# 01_MCU_ESP32C6.net
KiCad netlist of a schematic drawn in Altium Designer
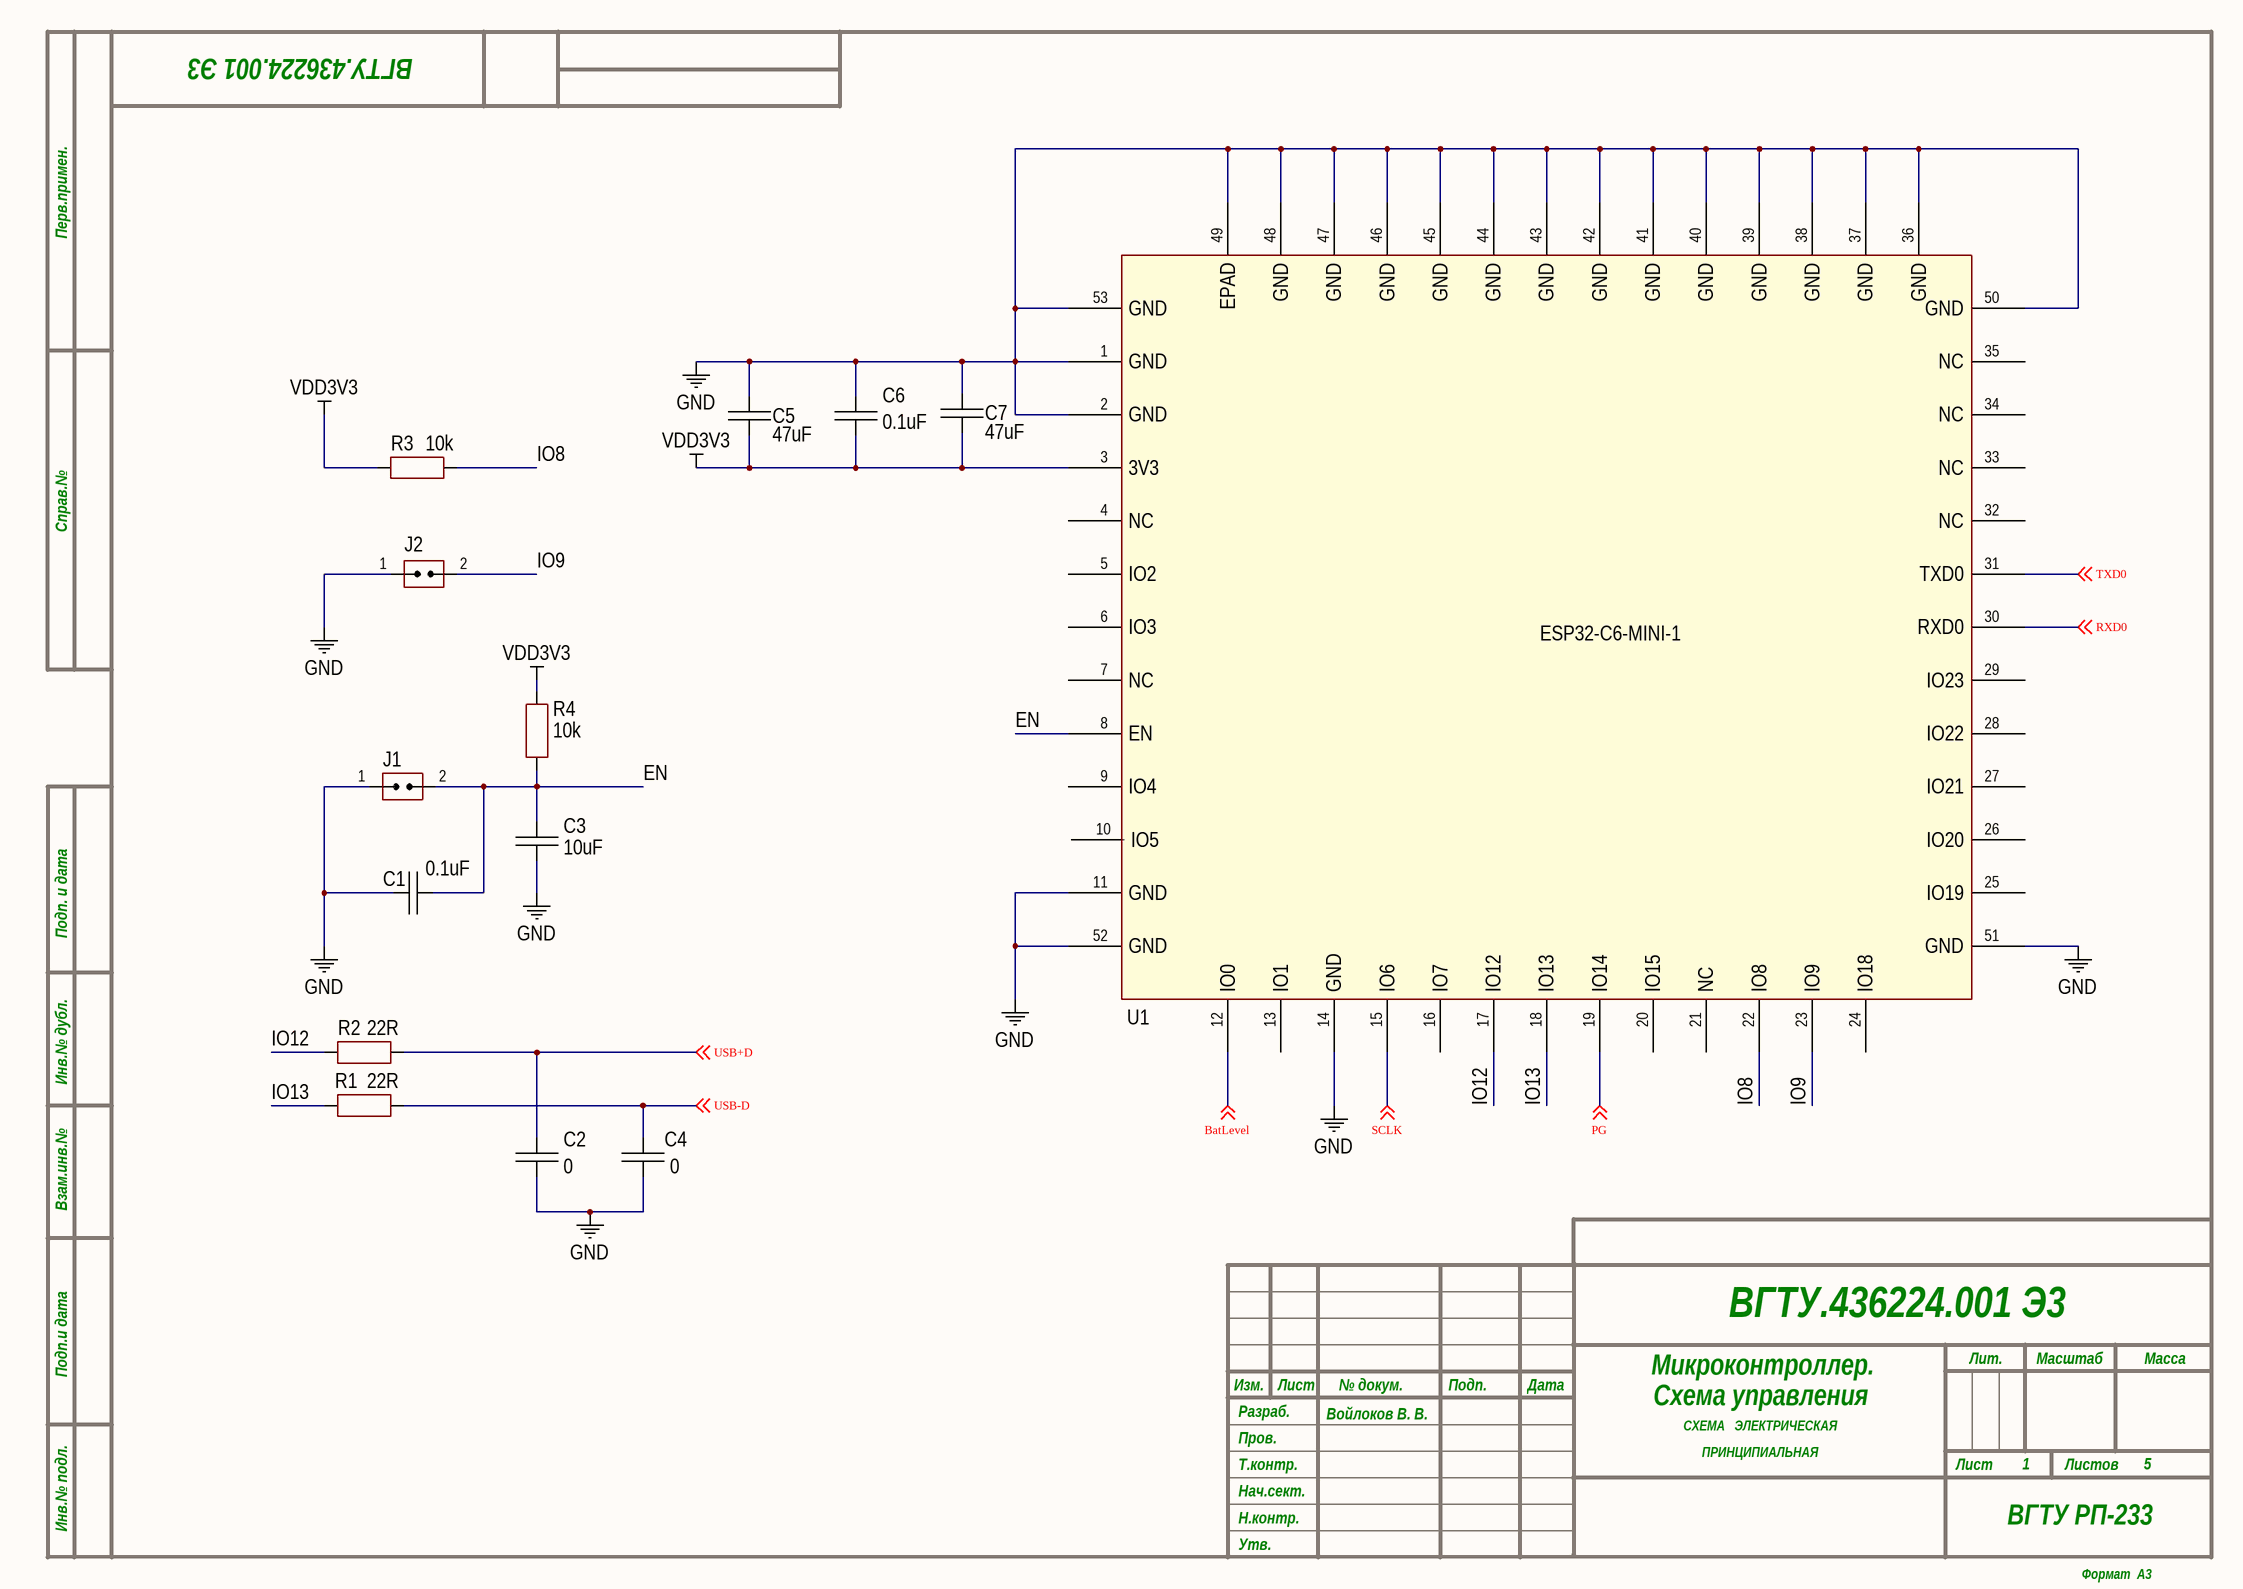
[diagram p0: 01_MCU_ESP32C6.SchDoc]

(export (version "E")
  (design (tool "Eeschema 10.0.6"))
  (components
    (comp (ref "C1")
      (value "0.1uF")
      (footprint "CAP: 0603")
      (fields
        (field (name "MANUFACTURER") "Yageo")
        (field (name "PARTNUMBER") "CC0603KRX7R7BB104")
        (field (name "VALUEMANUFACTURERPARTNUMBER") "Ceramic capacitor, 0.1uF, X7R, ±10%, 16V, 0603, -55...+125°C")
      )
      (libsource (lib "capacitor") (part "Ceramic_0603"))
    )
    (comp (ref "C2")
      (value "0")
      (footprint "CAP: 0603")
      (fields
        (field (name "MANUFACTURER") "Yageo")
        (field (name "PARTNUMBER") "CC0603KRX7R7BB104")
        (field (name "VALUEMANUFACTURERPARTNUMBER") "Ceramic capacitor, 0, X7R, ±10%, 16V, 0603, -55...+125°C")
      )
      (libsource (lib "capacitor") (part "Ceramic_0603"))
    )
    (comp (ref "C3")
      (value "10uF")
      (footprint "CAP: 0603")
      (fields
        (field (name "MANUFACTURER") "Yageo")
        (field (name "PARTNUMBER") "CC0603KRX7R7BB104")
        (field (name "VALUEMANUFACTURERPARTNUMBER") "Ceramic capacitor, 10uF, X7R, ±10%, 16V, 0603, -55...+125°C")
      )
      (libsource (lib "capacitor") (part "Ceramic_0603"))
    )
    (comp (ref "C4")
      (value "0")
      (footprint "CAP: 0603")
      (fields
        (field (name "MANUFACTURER") "Yageo")
        (field (name "PARTNUMBER") "CC0603KRX7R7BB104")
        (field (name "VALUEMANUFACTURERPARTNUMBER") "Ceramic capacitor, 0, X7R, ±10%, 16V, 0603, -55...+125°C")
      )
      (libsource (lib "capacitor") (part "Ceramic_0603"))
    )
    (comp (ref "C5")
      (value "47uF")
      (footprint "CAP: 0805")
      (fields
        (field (name "MANUFACTURER") "Yageo")
        (field (name "PARTNUMBER") "CC0805KRX7R7BB104")
        (field (name "VALUEMANUFACTURERPARTNUMBER") "Ceramic capacitor, 47uF, X7R, ±10%, 16V, 0805, -55...+125°C")
      )
      (libsource (lib "capacitor") (part "Ceramic_0805"))
    )
    (comp (ref "C6")
      (value "0.1uF")
      (footprint "CAP: 0603")
      (fields
        (field (name "MANUFACTURER") "Yageo")
        (field (name "PARTNUMBER") "CC0603KRX7R7BB104")
        (field (name "VALUEMANUFACTURERPARTNUMBER") "Ceramic capacitor, 0.1uF, X7R, ±10%, 16V, 0603, -55...+125°C")
      )
      (libsource (lib "capacitor") (part "Ceramic_0603"))
    )
    (comp (ref "C7")
      (value "47uF")
      (footprint "CAP: 0805")
      (fields
        (field (name "MANUFACTURER") "Yageo")
        (field (name "PARTNUMBER") "CC0805KRX7R7BB104")
        (field (name "VALUEMANUFACTURERPARTNUMBER") "Ceramic capacitor, 47uF, X7R, ±10%, 16V, 0805, -55...+125°C")
      )
      (libsource (lib "capacitor") (part "Ceramic_0805"))
    )
    (comp (ref "J1")
      (value "~")
      (footprint "CON: JUMPER x1")
      (libsource (lib "connector") (part "Jumper_single"))
    )
    (comp (ref "J2")
      (value "~")
      (footprint "CON: JUMPER x1")
      (libsource (lib "connector") (part "Jumper_single"))
    )
    (comp (ref "R1")
      (value "22R")
      (footprint "RES: 0603")
      (fields
        (field (name "MANUFACTURER") "Yageo")
        (field (name "PARTNUMBER") "RC0603JR-07100RL")
        (field (name "VALUEMANUFACTURERPARTNUMBER") "Resistor film, 22R, ±5%, 0603, 0.1W, -55...+125°C")
      )
      (libsource (lib "resistor") (part "Resistor_0603"))
    )
    (comp (ref "R2")
      (value "22R")
      (footprint "RES: 0603")
      (fields
        (field (name "MANUFACTURER") "Yageo")
        (field (name "PARTNUMBER") "RC0603JR-07100RL")
        (field (name "VALUEMANUFACTURERPARTNUMBER") "Resistor film, 22R, ±5%, 0603, 0.1W, -55...+125°C")
      )
      (libsource (lib "resistor") (part "Resistor_0603"))
    )
    (comp (ref "R3")
      (value "10k")
      (footprint "RES: 0603")
      (fields
        (field (name "MANUFACTURER") "Yageo")
        (field (name "PARTNUMBER") "RC0603JR-07100RL")
        (field (name "VALUEMANUFACTURERPARTNUMBER") "Resistor film, 10k, ±5%, 0603, 0.1W, -55...+125°C")
      )
      (libsource (lib "resistor") (part "Resistor_0603"))
    )
    (comp (ref "R4")
      (value "10k")
      (footprint "RES: 0603")
      (fields
        (field (name "MANUFACTURER") "Yageo")
        (field (name "PARTNUMBER") "RC0603JR-07100RL")
        (field (name "VALUEMANUFACTURERPARTNUMBER") "Resistor film, 10k, ±5%, 0603, 0.1W, -55...+125°C")
      )
      (libsource (lib "") (part "Resistor_0603_1"))
    )
    (comp (ref "U1")
      (value "ESP32-C6-MINI-1")
      (footprint "ESP32-C6_EXP")
      (libsource (lib "MyLib") (part "ESP32-C6-MINI-1"))
    )
  )
  (nets
    (net (code "1") (name "/EN") (class "Default")
      (node (ref "C1") (pin "1") (pinfunction "1_1") (pintype "passive"))
      (node (ref "C3") (pin "2") (pinfunction "2_2") (pintype "passive"))
      (node (ref "J1") (pin "2") (pinfunction "IN_2") (pintype "passive"))
      (node (ref "R4") (pin "1") (pinfunction "1_1") (pintype "passive"))
      (node (ref "U1") (pin "8") (pinfunction "EN_8") (pintype "passive"))
    )
    (net (code "2") (name "/IO8") (class "Default")
      (node (ref "R3") (pin "1") (pinfunction "1_1") (pintype "passive"))
      (node (ref "U1") (pin "22") (pinfunction "IO8_22") (pintype "passive"))
    )
    (net (code "3") (name "/IO9") (class "Default")
      (node (ref "J2") (pin "2") (pinfunction "IN_2") (pintype "passive"))
      (node (ref "U1") (pin "23") (pinfunction "IO9_23") (pintype "passive"))
    )
    (net (code "4") (name "/IO12") (class "Default")
      (node (ref "R2") (pin "2") (pinfunction "2_2") (pintype "passive"))
      (node (ref "U1") (pin "17") (pinfunction "IO12_17") (pintype "passive"))
    )
    (net (code "5") (name "/IO13") (class "Default")
      (node (ref "R1") (pin "2") (pinfunction "2_2") (pintype "passive"))
      (node (ref "U1") (pin "18") (pinfunction "IO13_18") (pintype "passive"))
    )
    (net (code "6") (name "BatLevel") (class "Default")
      (node (ref "U1") (pin "12") (pinfunction "IO0_12") (pintype "passive"))
    )
    (net (code "7") (name "GND") (class "Default")
      (node (ref "C1") (pin "2") (pinfunction "2_2") (pintype "passive"))
      (node (ref "C2") (pin "2") (pinfunction "2_2") (pintype "passive"))
      (node (ref "C3") (pin "1") (pinfunction "1_1") (pintype "passive"))
      (node (ref "C4") (pin "2") (pinfunction "2_2") (pintype "passive"))
      (node (ref "C5") (pin "2") (pinfunction "2_2") (pintype "passive"))
      (node (ref "C6") (pin "2") (pinfunction "2_2") (pintype "passive"))
      (node (ref "C7") (pin "2") (pinfunction "2_2") (pintype "passive"))
      (node (ref "J1") (pin "1") (pinfunction "IN_1") (pintype "passive"))
      (node (ref "J2") (pin "1") (pinfunction "IN_1") (pintype "passive"))
      (node (ref "U1") (pin "1") (pinfunction "GND_1") (pintype "passive"))
      (node (ref "U1") (pin "11") (pinfunction "GND_11") (pintype "passive"))
      (node (ref "U1") (pin "14") (pinfunction "GND_14") (pintype "passive"))
      (node (ref "U1") (pin "2") (pinfunction "GND_2") (pintype "passive"))
      (node (ref "U1") (pin "36") (pinfunction "GND_36") (pintype "passive"))
      (node (ref "U1") (pin "37") (pinfunction "GND_37") (pintype "passive"))
      (node (ref "U1") (pin "38") (pinfunction "GND_38") (pintype "passive"))
      (node (ref "U1") (pin "39") (pinfunction "GND_39") (pintype "passive"))
      (node (ref "U1") (pin "40") (pinfunction "GND_40") (pintype "passive"))
      (node (ref "U1") (pin "41") (pinfunction "GND_41") (pintype "passive"))
      (node (ref "U1") (pin "42") (pinfunction "GND_42") (pintype "passive"))
      (node (ref "U1") (pin "43") (pinfunction "GND_43") (pintype "passive"))
      (node (ref "U1") (pin "44") (pinfunction "GND_44") (pintype "passive"))
      (node (ref "U1") (pin "45") (pinfunction "GND_45") (pintype "passive"))
      (node (ref "U1") (pin "46") (pinfunction "GND_46") (pintype "passive"))
      (node (ref "U1") (pin "47") (pinfunction "GND_47") (pintype "passive"))
      (node (ref "U1") (pin "48") (pinfunction "GND_48") (pintype "passive"))
      (node (ref "U1") (pin "49") (pinfunction "EPAD_49") (pintype "passive"))
      (node (ref "U1") (pin "50") (pinfunction "GND_50") (pintype "passive"))
      (node (ref "U1") (pin "51") (pinfunction "GND_51") (pintype "passive"))
      (node (ref "U1") (pin "52") (pinfunction "GND_52") (pintype "passive"))
      (node (ref "U1") (pin "53") (pinfunction "GND_53") (pintype "passive"))
    )
    (net (code "8") (name "PG") (class "Default")
      (node (ref "U1") (pin "19") (pinfunction "IO14_19") (pintype "passive"))
    )
    (net (code "9") (name "RXD0") (class "Default")
      (node (ref "U1") (pin "30") (pinfunction "RXD0_30") (pintype "passive"))
    )
    (net (code "10") (name "SCLK") (class "Default")
      (node (ref "U1") (pin "15") (pinfunction "IO6_15") (pintype "passive"))
    )
    (net (code "11") (name "TXD0") (class "Default")
      (node (ref "U1") (pin "31") (pinfunction "TXD0_31") (pintype "passive"))
    )
    (net (code "12") (name "USB+D") (class "Default")
      (node (ref "C2") (pin "1") (pinfunction "1_1") (pintype "passive"))
      (node (ref "R2") (pin "1") (pinfunction "1_1") (pintype "passive"))
    )
    (net (code "13") (name "USB-D") (class "Default")
      (node (ref "C4") (pin "1") (pinfunction "1_1") (pintype "passive"))
      (node (ref "R1") (pin "1") (pinfunction "1_1") (pintype "passive"))
    )
    (net (code "14") (name "VDD3V3") (class "Default")
      (node (ref "C5") (pin "1") (pinfunction "1_1") (pintype "passive"))
      (node (ref "C6") (pin "1") (pinfunction "1_1") (pintype "passive"))
      (node (ref "C7") (pin "1") (pinfunction "1_1") (pintype "passive"))
      (node (ref "R3") (pin "2") (pinfunction "2_2") (pintype "passive"))
      (node (ref "R4") (pin "2") (pinfunction "2_2") (pintype "passive"))
      (node (ref "U1") (pin "3") (pinfunction "3V3_3") (pintype "passive"))
    )
    (net (code "15") (name "unconnected-(U1-IO1-Pad13)") (class "Default")
      (node (ref "U1") (pin "13") (pinfunction "IO1_13") (pintype "passive"))
    )
    (net (code "16") (name "unconnected-(U1-IO2-Pad5)") (class "Default")
      (node (ref "U1") (pin "5") (pinfunction "IO2_5") (pintype "passive"))
    )
    (net (code "17") (name "unconnected-(U1-IO3-Pad6)") (class "Default")
      (node (ref "U1") (pin "6") (pinfunction "IO3_6") (pintype "passive"))
    )
    (net (code "18") (name "unconnected-(U1-IO4-Pad9)") (class "Default")
      (node (ref "U1") (pin "9") (pinfunction "IO4_9") (pintype "passive"))
    )
    (net (code "19") (name "unconnected-(U1-IO5-Pad10)") (class "Default")
      (node (ref "U1") (pin "10") (pinfunction "IO5_10") (pintype "passive"))
    )
    (net (code "20") (name "unconnected-(U1-IO7-Pad16)") (class "Default")
      (node (ref "U1") (pin "16") (pinfunction "IO7_16") (pintype "passive"))
    )
    (net (code "21") (name "unconnected-(U1-IO15-Pad20)") (class "Default")
      (node (ref "U1") (pin "20") (pinfunction "IO15_20") (pintype "passive"))
    )
    (net (code "22") (name "unconnected-(U1-IO18-Pad24)") (class "Default")
      (node (ref "U1") (pin "24") (pinfunction "IO18_24") (pintype "passive"))
    )
    (net (code "23") (name "unconnected-(U1-IO19-Pad25)") (class "Default")
      (node (ref "U1") (pin "25") (pinfunction "IO19_25") (pintype "passive"))
    )
    (net (code "24") (name "unconnected-(U1-IO20-Pad26)") (class "Default")
      (node (ref "U1") (pin "26") (pinfunction "IO20_26") (pintype "passive"))
    )
    (net (code "25") (name "unconnected-(U1-IO21-Pad27)") (class "Default")
      (node (ref "U1") (pin "27") (pinfunction "IO21_27") (pintype "passive"))
    )
    (net (code "26") (name "unconnected-(U1-IO22-Pad28)") (class "Default")
      (node (ref "U1") (pin "28") (pinfunction "IO22_28") (pintype "passive"))
    )
    (net (code "27") (name "unconnected-(U1-IO23-Pad29)") (class "Default")
      (node (ref "U1") (pin "29") (pinfunction "IO23_29") (pintype "passive"))
    )
    (net (code "28") (name "unconnected-(U1-NC-Pad4)") (class "Default")
      (node (ref "U1") (pin "4") (pinfunction "NC_4") (pintype "passive"))
    )
    (net (code "29") (name "unconnected-(U1-NC-Pad7)") (class "Default")
      (node (ref "U1") (pin "7") (pinfunction "NC_7") (pintype "passive"))
    )
    (net (code "30") (name "unconnected-(U1-NC-Pad21)") (class "Default")
      (node (ref "U1") (pin "21") (pinfunction "NC_21") (pintype "passive"))
    )
    (net (code "31") (name "unconnected-(U1-NC-Pad32)") (class "Default")
      (node (ref "U1") (pin "32") (pinfunction "NC_32") (pintype "passive"))
    )
    (net (code "32") (name "unconnected-(U1-NC-Pad33)") (class "Default")
      (node (ref "U1") (pin "33") (pinfunction "NC_33") (pintype "passive"))
    )
    (net (code "33") (name "unconnected-(U1-NC-Pad34)") (class "Default")
      (node (ref "U1") (pin "34") (pinfunction "NC_34") (pintype "passive"))
    )
    (net (code "34") (name "unconnected-(U1-NC-Pad35)") (class "Default")
      (node (ref "U1") (pin "35") (pinfunction "NC_35") (pintype "passive"))
    )
  )
)
